# Microcontroller_and_Memory.net
KiCad netlist of a schematic drawn in Altium Designer
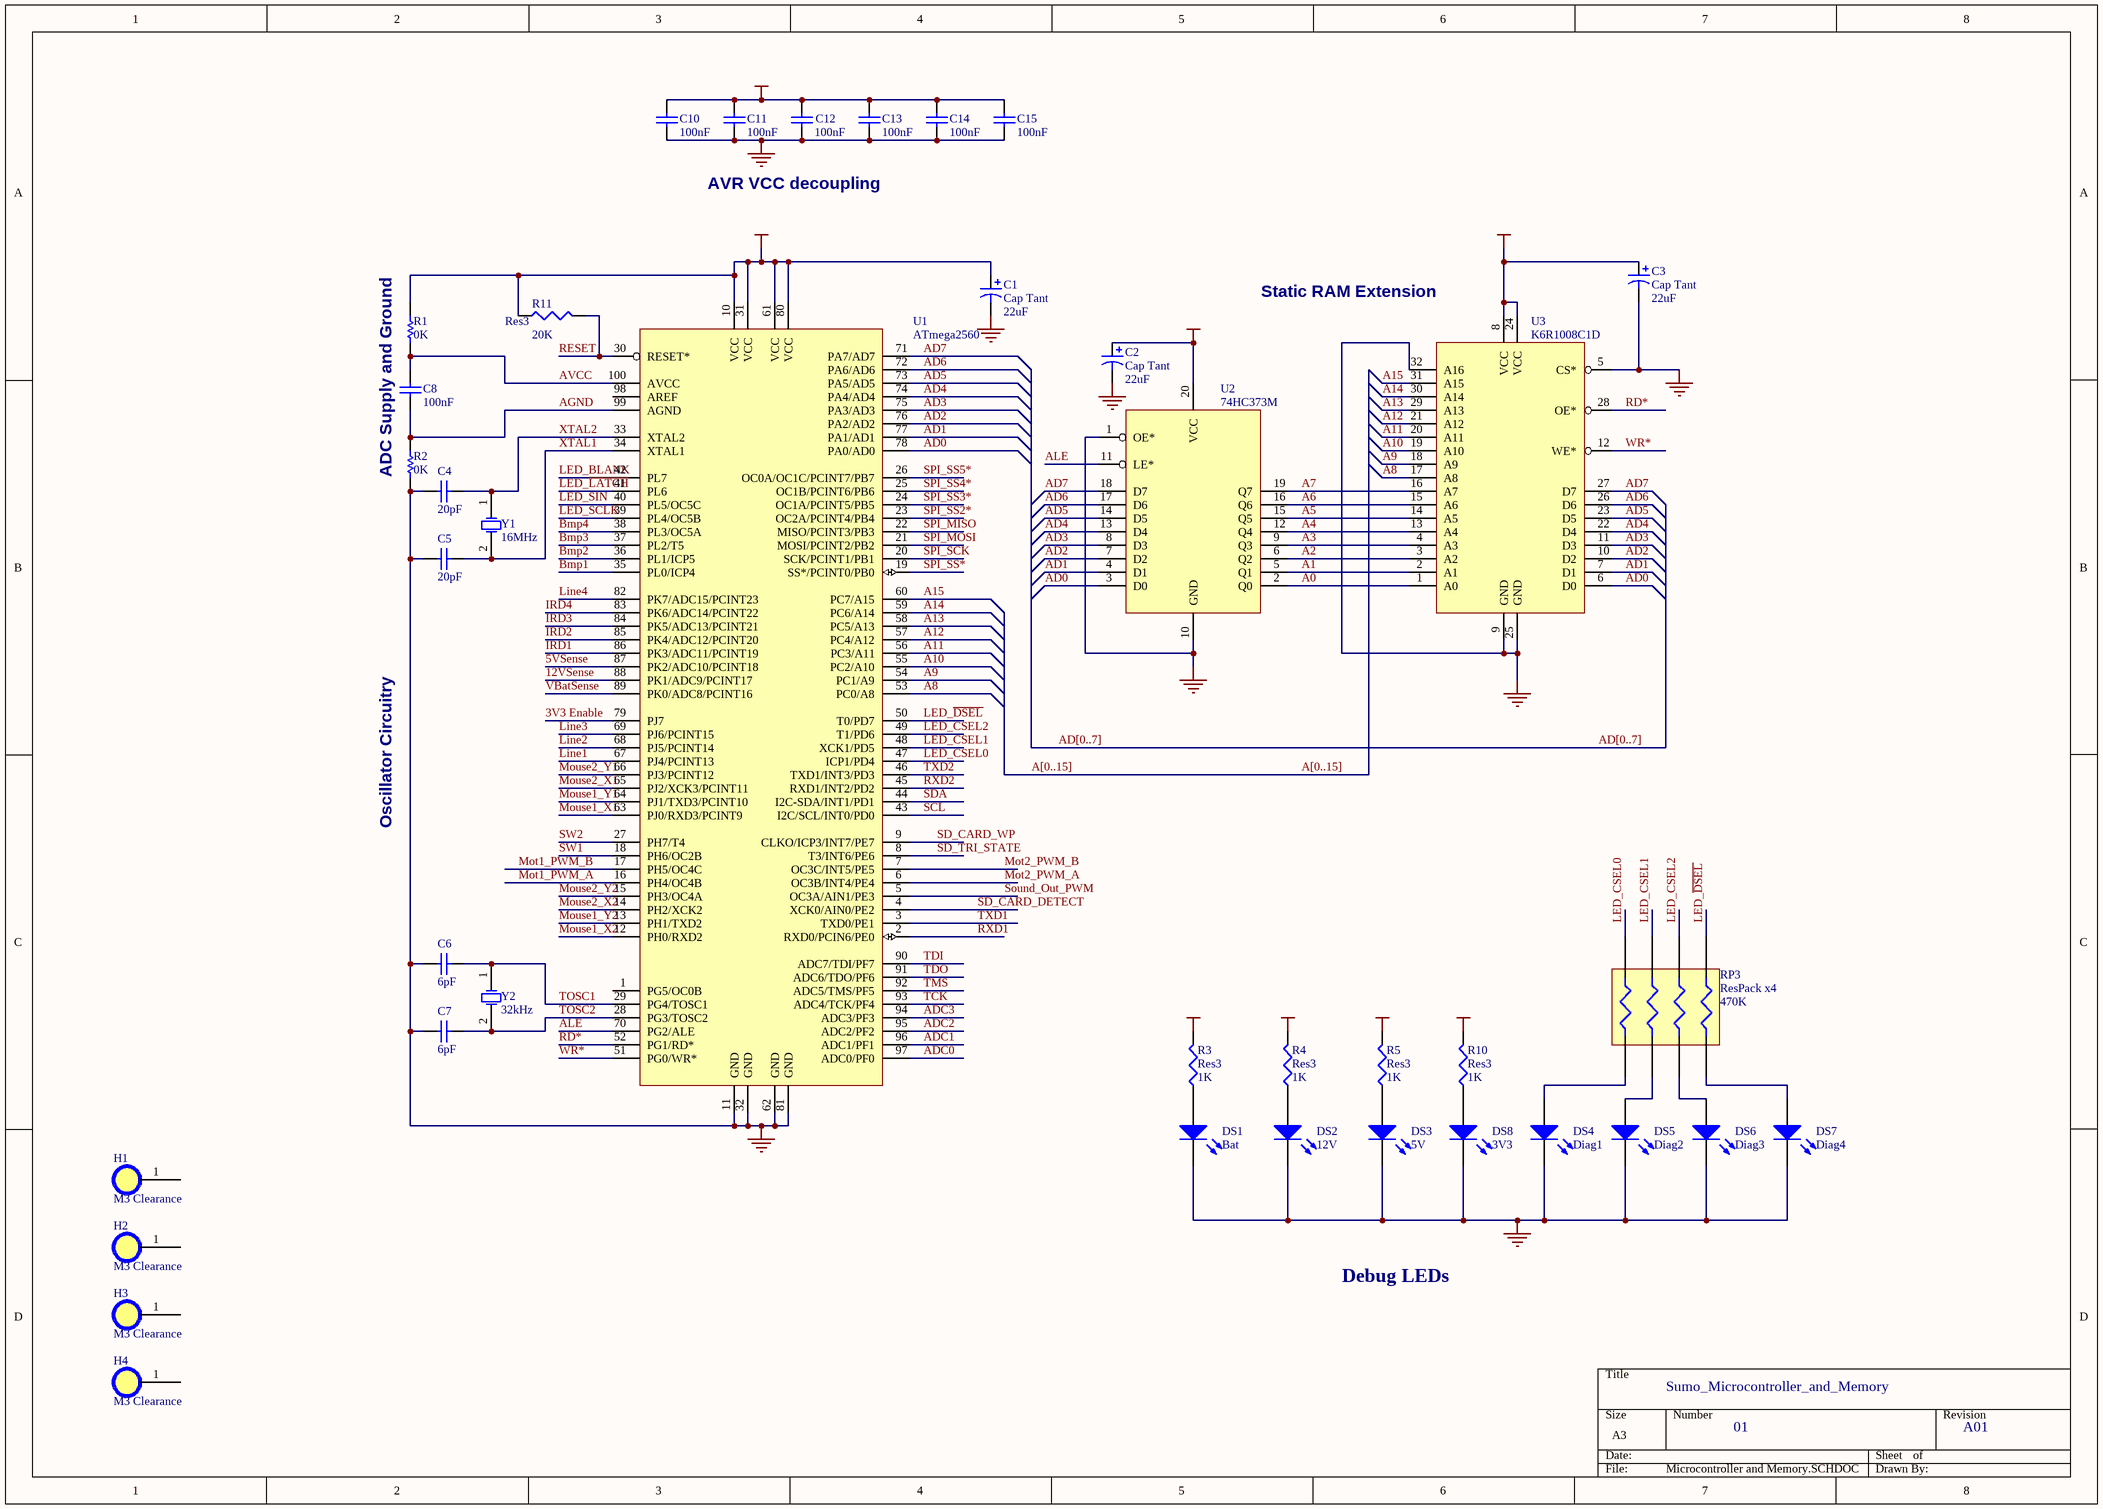
[diagram p0: Microcontroller and Memory.SCHDOC]

(export (version "E")
  (design (tool "Eeschema 10.0.6"))
  (components
    (comp (ref "C1")
      (value "Cap Tant")
      (footprint "CC4532-1812")
      (description "Polarized Capacitor (Axial)")
      (fields (field (name "ALTIUM_VALUE") "22uF") (field (name "PUBLISHER") "Altium Limited"))
      (libsource (lib "Miscellaneous Devices") (part "Cap Pol2"))
    )
    (comp (ref "C2")
      (value "Cap Tant")
      (footprint "CC4532-1812")
      (description "Polarized Capacitor (Axial)")
      (fields (field (name "ALTIUM_VALUE") "22uF") (field (name "PUBLISHER") "Altium Limited"))
      (libsource (lib "Miscellaneous Devices") (part "Cap Pol2"))
    )
    (comp (ref "C3")
      (value "Cap Tant")
      (footprint "CC4532-1812")
      (description "Polarized Capacitor (Axial)")
      (fields (field (name "ALTIUM_VALUE") "22uF") (field (name "PUBLISHER") "Altium Limited"))
      (libsource (lib "Miscellaneous Devices") (part "Cap Pol2"))
    )
    (comp (ref "C4")
      (value "20pF")
      (footprint "CC2012-0805")
      (description "Capacitor")
      (fields (field (name "PUBLISHER") "Altium Limited"))
      (libsource (lib "Miscellaneous Devices") (part "Cap"))
    )
    (comp (ref "C5")
      (value "20pF")
      (footprint "CC2012-0805")
      (description "Capacitor")
      (fields (field (name "PUBLISHER") "Altium Limited"))
      (libsource (lib "Miscellaneous Devices") (part "Cap"))
    )
    (comp (ref "C6")
      (value "6pF")
      (footprint "CC2012-0805")
      (description "Capacitor")
      (fields (field (name "PUBLISHER") "Altium Limited"))
      (libsource (lib "Miscellaneous Devices") (part "Cap"))
    )
    (comp (ref "C7")
      (value "6pF")
      (footprint "CC2012-0805")
      (description "Capacitor")
      (fields (field (name "PUBLISHER") "Altium Limited"))
      (libsource (lib "Miscellaneous Devices") (part "Cap"))
    )
    (comp (ref "C8")
      (value "100nF")
      (footprint "CC2012-0805")
      (description "Capacitor")
      (fields (field (name "PUBLISHER") "Altium Limited"))
      (libsource (lib "Miscellaneous Devices") (part "Cap"))
    )
    (comp (ref "C10")
      (value "100nF")
      (footprint "CC2012-0805")
      (description "Capacitor (Semiconductor SIM Model)")
      (fields (field (name "Comment") "Cap Semi") (field (name "PUBLISHER") "Altium Limited"))
      (libsource (lib "Miscellaneous Devices") (part "Cap Semi"))
    )
    (comp (ref "C11")
      (value "100nF")
      (footprint "CC2012-0805")
      (description "Capacitor (Semiconductor SIM Model)")
      (fields (field (name "Comment") "Cap Semi") (field (name "PUBLISHER") "Altium Limited"))
      (libsource (lib "Miscellaneous Devices") (part "Cap Semi"))
    )
    (comp (ref "C12")
      (value "100nF")
      (footprint "CC2012-0805")
      (description "Capacitor (Semiconductor SIM Model)")
      (fields (field (name "Comment") "Cap Semi") (field (name "PUBLISHER") "Altium Limited"))
      (libsource (lib "Miscellaneous Devices") (part "Cap Semi"))
    )
    (comp (ref "C13")
      (value "100nF")
      (footprint "CC2012-0805")
      (description "Capacitor (Semiconductor SIM Model)")
      (fields (field (name "Comment") "Cap Semi") (field (name "PUBLISHER") "Altium Limited"))
      (libsource (lib "Miscellaneous Devices") (part "Cap Semi"))
    )
    (comp (ref "C14")
      (value "100nF")
      (footprint "CC2012-0805")
      (description "Capacitor (Semiconductor SIM Model)")
      (fields (field (name "Comment") "Cap Semi") (field (name "PUBLISHER") "Altium Limited"))
      (libsource (lib "Miscellaneous Devices") (part "Cap Semi"))
    )
    (comp (ref "C15")
      (value "100nF")
      (footprint "CC2012-0805")
      (description "Capacitor (Semiconductor SIM Model)")
      (fields (field (name "Comment") "Cap Semi") (field (name "PUBLISHER") "Altium Limited"))
      (libsource (lib "Miscellaneous Devices") (part "Cap Semi"))
    )
    (comp (ref "DS1")
      (value "Bat")
      (footprint "SMD _LED")
      (description "Typical BLUE SiC LED")
      (fields (field (name "PUBLISHER") "Altium Limited"))
      (libsource (lib "Miscellaneous Devices") (part "LED3"))
    )
    (comp (ref "DS2")
      (value "12V")
      (footprint "SMD _LED")
      (description "Typical BLUE SiC LED")
      (fields (field (name "PUBLISHER") "Altium Limited"))
      (libsource (lib "Miscellaneous Devices") (part "LED3"))
    )
    (comp (ref "DS3")
      (value "5V")
      (footprint "SMD _LED")
      (description "Typical BLUE SiC LED")
      (fields (field (name "PUBLISHER") "Altium Limited"))
      (libsource (lib "Miscellaneous Devices") (part "LED3"))
    )
    (comp (ref "DS4")
      (value "Diag1")
      (footprint "SMD _LED")
      (description "Typical BLUE SiC LED")
      (fields (field (name "PUBLISHER") "Altium Limited"))
      (libsource (lib "Miscellaneous Devices") (part "LED3"))
    )
    (comp (ref "DS5")
      (value "Diag2")
      (footprint "SMD _LED")
      (description "Typical BLUE SiC LED")
      (fields (field (name "PUBLISHER") "Altium Limited"))
      (libsource (lib "Miscellaneous Devices") (part "LED3"))
    )
    (comp (ref "DS6")
      (value "Diag3")
      (footprint "SMD _LED")
      (description "Typical BLUE SiC LED")
      (fields (field (name "PUBLISHER") "Altium Limited"))
      (libsource (lib "Miscellaneous Devices") (part "LED3"))
    )
    (comp (ref "DS7")
      (value "Diag4")
      (footprint "SMD _LED")
      (description "Typical BLUE SiC LED")
      (fields (field (name "PUBLISHER") "Altium Limited"))
      (libsource (lib "Miscellaneous Devices") (part "LED3"))
    )
    (comp (ref "DS8")
      (value "3V3")
      (footprint "SMD _LED")
      (description "Typical BLUE SiC LED")
      (fields (field (name "PUBLISHER") "Altium Limited"))
      (libsource (lib "Miscellaneous Devices") (part "LED3"))
    )
    (comp (ref "H1")
      (value "M3 Clearance")
      (footprint "M3 Clearance")
      (description "3.2mm ID clearance hole for M3 screw")
      (libsource (lib "Sumo") (part "M3 Clearance hole"))
    )
    (comp (ref "H2")
      (value "M3 Clearance")
      (footprint "M3 Clearance")
      (description "3.2mm ID clearance hole for M3 screw")
      (libsource (lib "Sumo") (part "M3 Clearance hole"))
    )
    (comp (ref "H3")
      (value "M3 Clearance")
      (footprint "M3 Clearance")
      (description "3.2mm ID clearance hole for M3 screw")
      (libsource (lib "Sumo") (part "M3 Clearance hole"))
    )
    (comp (ref "H4")
      (value "M3 Clearance")
      (footprint "M3 Clearance")
      (description "3.2mm ID clearance hole for M3 screw")
      (libsource (lib "Sumo") (part "M3 Clearance hole"))
    )
    (comp (ref "R1")
      (value "0K")
      (footprint "R2012-0805")
      (description "Resistor")
      (fields (field (name "PUBLISHER") "Altium Limited"))
      (libsource (lib "Miscellaneous Devices") (part "Res1"))
    )
    (comp (ref "R2")
      (value "0K")
      (footprint "R2012-0805")
      (description "Resistor")
      (fields (field (name "PUBLISHER") "Altium Limited"))
      (libsource (lib "Miscellaneous Devices") (part "Res1"))
    )
    (comp (ref "R3")
      (value "Res3")
      (footprint "R2012-0805")
      (description "Resistor")
      (fields (field (name "ALTIUM_VALUE") "1K") (field (name "PUBLISHER") "Altium Limited"))
      (libsource (lib "Miscellaneous Devices") (part "Res3"))
    )
    (comp (ref "R4")
      (value "Res3")
      (footprint "R2012-0805")
      (description "Resistor")
      (fields (field (name "ALTIUM_VALUE") "1K") (field (name "PUBLISHER") "Altium Limited"))
      (libsource (lib "Miscellaneous Devices") (part "Res3"))
    )
    (comp (ref "R5")
      (value "Res3")
      (footprint "R2012-0805")
      (description "Resistor")
      (fields (field (name "ALTIUM_VALUE") "1K") (field (name "PUBLISHER") "Altium Limited"))
      (libsource (lib "Miscellaneous Devices") (part "Res3"))
    )
    (comp (ref "R10")
      (value "Res3")
      (footprint "R2012-0805")
      (description "Resistor")
      (fields (field (name "ALTIUM_VALUE") "1K") (field (name "PUBLISHER") "Altium Limited"))
      (libsource (lib "Miscellaneous Devices") (part "Res3"))
    )
    (comp (ref "R11")
      (value "Res3")
      (footprint "R2012-0805")
      (description "Resistor")
      (fields (field (name "ALTIUM_VALUE") "20K") (field (name "PUBLISHER") "Altium Limited"))
      (libsource (lib "Miscellaneous Devices") (part "Res3"))
    )
    (comp (ref "RP3")
      (value "ResPack x4")
      (footprint "4x0805 Resistor pack")
      (fields (field (name "ALTIUM_VALUE") "470K"))
      (libsource (lib "Sumo") (part "ResPack x4"))
    )
    (comp (ref "U1")
      (value "ATmega2560")
      (footprint "F-QFP14X14-G100/Z17N")
      (description "Atmel ATmega2560 MCU")
      (libsource (lib "Sumo") (part "ATmega2560"))
    )
    (comp (ref "U2")
      (value "74HC373M")
      (footprint "SO-G20/Y1.45")
      (description "Octal 8-bit D-type Latch")
      (libsource (lib "Schematic Library") (part "74373"))
    )
    (comp (ref "U3")
      (value "K6R1008C1D")
      (footprint "SO-G32/Y1.45")
      (description "Samsung 128Kx8 High-Speed Static RAM")
      (libsource (lib "Schematic Library") (part "K6R1008C1D"))
    )
    (comp (ref "Y1")
      (value "16MHz")
      (footprint "Crystal HC49SLF")
      (description "Crystal Oscillator")
      (fields (field (name "PUBLISHER") "Altium Limited"))
      (libsource (lib "Miscellaneous Devices") (part "XTAL"))
    )
    (comp (ref "Y2")
      (value "32kHz")
      (footprint "Crystal CFS206")
      (description "Crystal Oscillator")
      (fields (field (name "PUBLISHER") "Altium Limited"))
      (libsource (lib "Miscellaneous Devices") (part "XTAL"))
    )
  )
  (nets
    (net (code "1") (name "/3V3 Enable") (class "Default")
      (node (ref "U1") (pin "79") (pinfunction "PJ7_79") (pintype "passive"))
    )
    (net (code "2") (name "/5VSense") (class "Default")
      (node (ref "U1") (pin "87") (pinfunction "PK2/ADC10/PCINT18_87") (pintype "passive"))
    )
    (net (code "3") (name "/12VSense") (class "Default")
      (node (ref "U1") (pin "88") (pinfunction "PK1/ADC9/PCINT17_88") (pintype "passive"))
    )
    (net (code "4") (name "/A0") (class "Default")
      (node (ref "U2") (pin "2") (pinfunction "Q0_2") (pintype "passive"))
      (node (ref "U3") (pin "1") (pinfunction "A0_1") (pintype "passive"))
    )
    (net (code "5") (name "/A1") (class "Default")
      (node (ref "U2") (pin "5") (pinfunction "Q1_5") (pintype "passive"))
      (node (ref "U3") (pin "2") (pinfunction "A1_2") (pintype "passive"))
    )
    (net (code "6") (name "/A2") (class "Default")
      (node (ref "U2") (pin "6") (pinfunction "Q2_6") (pintype "passive"))
      (node (ref "U3") (pin "3") (pinfunction "A2_3") (pintype "passive"))
    )
    (net (code "7") (name "/A3") (class "Default")
      (node (ref "U2") (pin "9") (pinfunction "Q3_9") (pintype "passive"))
      (node (ref "U3") (pin "4") (pinfunction "A3_4") (pintype "passive"))
    )
    (net (code "8") (name "/A4") (class "Default")
      (node (ref "U2") (pin "12") (pinfunction "Q4_12") (pintype "passive"))
      (node (ref "U3") (pin "13") (pinfunction "A4_13") (pintype "passive"))
    )
    (net (code "9") (name "/A5") (class "Default")
      (node (ref "U2") (pin "15") (pinfunction "Q5_15") (pintype "passive"))
      (node (ref "U3") (pin "14") (pinfunction "A5_14") (pintype "passive"))
    )
    (net (code "10") (name "/A6") (class "Default")
      (node (ref "U2") (pin "16") (pinfunction "Q6_16") (pintype "passive"))
      (node (ref "U3") (pin "15") (pinfunction "A6_15") (pintype "passive"))
    )
    (net (code "11") (name "/A7") (class "Default")
      (node (ref "U2") (pin "19") (pinfunction "Q7_19") (pintype "passive"))
      (node (ref "U3") (pin "16") (pinfunction "A7_16") (pintype "passive"))
    )
    (net (code "12") (name "/A8") (class "Default")
      (node (ref "U1") (pin "53") (pinfunction "PC0/A8_53") (pintype "passive"))
      (node (ref "U3") (pin "17") (pinfunction "A8_17") (pintype "passive"))
    )
    (net (code "13") (name "/A9") (class "Default")
      (node (ref "U1") (pin "54") (pinfunction "PC1/A9_54") (pintype "passive"))
      (node (ref "U3") (pin "18") (pinfunction "A9_18") (pintype "passive"))
    )
    (net (code "14") (name "/A10") (class "Default")
      (node (ref "U1") (pin "55") (pinfunction "PC2/A10_55") (pintype "passive"))
      (node (ref "U3") (pin "19") (pinfunction "A10_19") (pintype "passive"))
    )
    (net (code "15") (name "/A11") (class "Default")
      (node (ref "U1") (pin "56") (pinfunction "PC3/A11_56") (pintype "passive"))
      (node (ref "U3") (pin "20") (pinfunction "A11_20") (pintype "passive"))
    )
    (net (code "16") (name "/A12") (class "Default")
      (node (ref "U1") (pin "57") (pinfunction "PC4/A12_57") (pintype "passive"))
      (node (ref "U3") (pin "21") (pinfunction "A12_21") (pintype "passive"))
    )
    (net (code "17") (name "/A13") (class "Default")
      (node (ref "U1") (pin "58") (pinfunction "PC5/A13_58") (pintype "passive"))
      (node (ref "U3") (pin "29") (pinfunction "A13_29") (pintype "passive"))
    )
    (net (code "18") (name "/A14") (class "Default")
      (node (ref "U1") (pin "59") (pinfunction "PC6/A14_59") (pintype "passive"))
      (node (ref "U3") (pin "30") (pinfunction "A14_30") (pintype "passive"))
    )
    (net (code "19") (name "/A15") (class "Default")
      (node (ref "U1") (pin "60") (pinfunction "PC7/A15_60") (pintype "passive"))
      (node (ref "U3") (pin "31") (pinfunction "A15_31") (pintype "passive"))
    )
    (net (code "20") (name "/AD0") (class "Default")
      (node (ref "U1") (pin "78") (pinfunction "PA0/AD0_78") (pintype "passive"))
      (node (ref "U2") (pin "3") (pinfunction "D0_3") (pintype "passive"))
      (node (ref "U3") (pin "6") (pinfunction "D0_6") (pintype "passive"))
    )
    (net (code "21") (name "/AD1") (class "Default")
      (node (ref "U1") (pin "77") (pinfunction "PA1/AD1_77") (pintype "passive"))
      (node (ref "U2") (pin "4") (pinfunction "D1_4") (pintype "passive"))
      (node (ref "U3") (pin "7") (pinfunction "D1_7") (pintype "passive"))
    )
    (net (code "22") (name "/AD2") (class "Default")
      (node (ref "U1") (pin "76") (pinfunction "PA2/AD2_76") (pintype "passive"))
      (node (ref "U2") (pin "7") (pinfunction "D2_7") (pintype "passive"))
      (node (ref "U3") (pin "10") (pinfunction "D2_10") (pintype "passive"))
    )
    (net (code "23") (name "/AD3") (class "Default")
      (node (ref "U1") (pin "75") (pinfunction "PA3/AD3_75") (pintype "passive"))
      (node (ref "U2") (pin "8") (pinfunction "D3_8") (pintype "passive"))
      (node (ref "U3") (pin "11") (pinfunction "D3_11") (pintype "passive"))
    )
    (net (code "24") (name "/AD4") (class "Default")
      (node (ref "U1") (pin "74") (pinfunction "PA4/AD4_74") (pintype "passive"))
      (node (ref "U2") (pin "13") (pinfunction "D4_13") (pintype "passive"))
      (node (ref "U3") (pin "22") (pinfunction "D4_22") (pintype "passive"))
    )
    (net (code "25") (name "/AD5") (class "Default")
      (node (ref "U1") (pin "73") (pinfunction "PA5/AD5_73") (pintype "passive"))
      (node (ref "U2") (pin "14") (pinfunction "D5_14") (pintype "passive"))
      (node (ref "U3") (pin "23") (pinfunction "D5_23") (pintype "passive"))
    )
    (net (code "26") (name "/AD6") (class "Default")
      (node (ref "U1") (pin "72") (pinfunction "PA6/AD6_72") (pintype "passive"))
      (node (ref "U2") (pin "17") (pinfunction "D6_17") (pintype "passive"))
      (node (ref "U3") (pin "26") (pinfunction "D6_26") (pintype "passive"))
    )
    (net (code "27") (name "/AD7") (class "Default")
      (node (ref "U1") (pin "71") (pinfunction "PA7/AD7_71") (pintype "passive"))
      (node (ref "U2") (pin "18") (pinfunction "D7_18") (pintype "passive"))
      (node (ref "U3") (pin "27") (pinfunction "D7_27") (pintype "passive"))
    )
    (net (code "28") (name "/ADC0") (class "Default")
      (node (ref "U1") (pin "97") (pinfunction "ADC0/PF0_97") (pintype "passive"))
    )
    (net (code "29") (name "/ADC1") (class "Default")
      (node (ref "U1") (pin "96") (pinfunction "ADC1/PF1_96") (pintype "passive"))
    )
    (net (code "30") (name "/ADC2") (class "Default")
      (node (ref "U1") (pin "95") (pinfunction "ADC2/PF2_95") (pintype "passive"))
    )
    (net (code "31") (name "/ADC3") (class "Default")
      (node (ref "U1") (pin "94") (pinfunction "ADC3/PF3_94") (pintype "passive"))
    )
    (net (code "33") (name "/AGND") (class "Default")
      (node (ref "C8") (pin "2") (pinfunction "2_2") (pintype "passive"))
      (node (ref "R2") (pin "2") (pinfunction "2_2") (pintype "passive"))
      (node (ref "U1") (pin "99") (pinfunction "AGND_99") (pintype "passive"))
    )
    (net (code "34") (name "/ALE") (class "Default")
      (node (ref "U1") (pin "70") (pinfunction "PG2/ALE_70") (pintype "passive"))
      (node (ref "U2") (pin "11") (pinfunction "LE*_11") (pintype "passive"))
    )
    (net (code "35") (name "/AVCC") (class "Default")
      (node (ref "C8") (pin "1") (pinfunction "1_1") (pintype "passive"))
      (node (ref "R1") (pin "1") (pinfunction "1_1") (pintype "passive"))
      (node (ref "U1") (pin "100") (pinfunction "AVCC_100") (pintype "passive"))
    )
    (net (code "37") (name "/Bmp1") (class "Default")
      (node (ref "U1") (pin "35") (pinfunction "PL0/ICP4_35") (pintype "passive"))
    )
    (net (code "38") (name "/Bmp2") (class "Default")
      (node (ref "U1") (pin "36") (pinfunction "PL1/ICP5_36") (pintype "passive"))
    )
    (net (code "39") (name "/Bmp3") (class "Default")
      (node (ref "U1") (pin "37") (pinfunction "PL2/T5_37") (pintype "passive"))
    )
    (net (code "40") (name "/Bmp4") (class "Default")
      (node (ref "U1") (pin "38") (pinfunction "PL3/OC5A_38") (pintype "passive"))
    )
    (net (code "41") (name "/IRD1") (class "Default")
      (node (ref "U1") (pin "86") (pinfunction "PK3/ADC11/PCINT19_86") (pintype "passive"))
    )
    (net (code "42") (name "/IRD2") (class "Default")
      (node (ref "U1") (pin "85") (pinfunction "PK4/ADC12/PCINT20_85") (pintype "passive"))
    )
    (net (code "43") (name "/IRD3") (class "Default")
      (node (ref "U1") (pin "84") (pinfunction "PK5/ADC13/PCINT21_84") (pintype "passive"))
    )
    (net (code "44") (name "/IRD4") (class "Default")
      (node (ref "U1") (pin "83") (pinfunction "PK6/ADC14/PCINT22_83") (pintype "passive"))
    )
    (net (code "45") (name "/LED_BLANK") (class "Default")
      (node (ref "U1") (pin "42") (pinfunction "PL7_42") (pintype "passive"))
    )
    (net (code "46") (name "/LED_CSEL0") (class "Default")
      (node (ref "RP3") (pin "8") (pintype "passive"))
      (node (ref "U1") (pin "47") (pinfunction "ICP1/PD4_47") (pintype "passive"))
    )
    (net (code "47") (name "/LED_CSEL1") (class "Default")
      (node (ref "RP3") (pin "7") (pintype "passive"))
      (node (ref "U1") (pin "48") (pinfunction "XCK1/PD5_48") (pintype "passive"))
    )
    (net (code "48") (name "/LED_CSEL2") (class "Default")
      (node (ref "RP3") (pin "6") (pintype "passive"))
      (node (ref "U1") (pin "49") (pinfunction "T1/PD6_49") (pintype "passive"))
    )
    (net (code "49") (name "/LED_SCLK") (class "Default")
      (node (ref "U1") (pin "39") (pinfunction "PL4/OC5B_39") (pintype "passive"))
    )
    (net (code "50") (name "/LED_SIN") (class "Default")
      (node (ref "U1") (pin "40") (pinfunction "PL5/OC5C_40") (pintype "passive"))
    )
    (net (code "51") (name "/LED_~{DSEL}") (class "Default")
      (node (ref "RP3") (pin "5") (pintype "passive"))
      (node (ref "U1") (pin "50") (pinfunction "T0/PD7_50") (pintype "passive"))
    )
    (net (code "52") (name "/LED_~{LATCH}") (class "Default")
      (node (ref "U1") (pin "41") (pinfunction "PL6_41") (pintype "passive"))
    )
    (net (code "53") (name "/Line1") (class "Default")
      (node (ref "U1") (pin "67") (pinfunction "PJ4/PCINT13_67") (pintype "passive"))
    )
    (net (code "54") (name "/Line2") (class "Default")
      (node (ref "U1") (pin "68") (pinfunction "PJ5/PCINT14_68") (pintype "passive"))
    )
    (net (code "55") (name "/Line3") (class "Default")
      (node (ref "U1") (pin "69") (pinfunction "PJ6/PCINT15_69") (pintype "passive"))
    )
    (net (code "56") (name "/Line4") (class "Default")
      (node (ref "U1") (pin "82") (pinfunction "PK7/ADC15/PCINT23_82") (pintype "passive"))
    )
    (net (code "57") (name "/Mot1_PWM_A") (class "Default")
      (node (ref "U1") (pin "16") (pinfunction "PH4/OC4B_16") (pintype "passive"))
    )
    (net (code "58") (name "/Mot1_PWM_B") (class "Default")
      (node (ref "U1") (pin "17") (pinfunction "PH5/OC4C_17") (pintype "passive"))
    )
    (net (code "59") (name "/Mot2_PWM_A") (class "Default")
      (node (ref "U1") (pin "6") (pinfunction "OC3B/INT4/PE4_6") (pintype "passive"))
    )
    (net (code "60") (name "/Mot2_PWM_B") (class "Default")
      (node (ref "U1") (pin "7") (pinfunction "OC3C/INT5/PE5_7") (pintype "passive"))
    )
    (net (code "61") (name "/Mouse1_X1") (class "Default")
      (node (ref "U1") (pin "63") (pinfunction "PJ0/RXD3/PCINT9_63") (pintype "passive"))
    )
    (net (code "62") (name "/Mouse1_X2") (class "Default")
      (node (ref "U1") (pin "12") (pinfunction "PH0/RXD2_12") (pintype "passive"))
    )
    (net (code "63") (name "/Mouse1_Y1") (class "Default")
      (node (ref "U1") (pin "64") (pinfunction "PJ1/TXD3/PCINT10_64") (pintype "passive"))
    )
    (net (code "64") (name "/Mouse1_Y2") (class "Default")
      (node (ref "U1") (pin "13") (pinfunction "PH1/TXD2_13") (pintype "passive"))
    )
    (net (code "65") (name "/Mouse2_X1") (class "Default")
      (node (ref "U1") (pin "65") (pinfunction "PJ2/XCK3/PCINT11_65") (pintype "passive"))
    )
    (net (code "66") (name "/Mouse2_X2") (class "Default")
      (node (ref "U1") (pin "14") (pinfunction "PH2/XCK2_14") (pintype "passive"))
    )
    (net (code "67") (name "/Mouse2_Y1") (class "Default")
      (node (ref "U1") (pin "66") (pinfunction "PJ3/PCINT12_66") (pintype "passive"))
    )
    (net (code "68") (name "/Mouse2_Y2") (class "Default")
      (node (ref "U1") (pin "15") (pinfunction "PH3/OC4A_15") (pintype "passive"))
    )
    (net (code "69") (name "/RD*") (class "Default")
      (node (ref "U1") (pin "52") (pinfunction "PG1/RD*_52") (pintype "passive"))
      (node (ref "U3") (pin "28") (pinfunction "OE*_28") (pintype "passive"))
    )
    (net (code "70") (name "/RESET") (class "Default")
      (node (ref "R11") (pin "2") (pinfunction "2_2") (pintype "passive"))
      (node (ref "U1") (pin "30") (pinfunction "RESET*_30") (pintype "passive"))
    )
    (net (code "71") (name "/RXD1") (class "Default")
      (node (ref "U1") (pin "2") (pinfunction "RXD0/PCIN6/PE0_2") (pintype "bidirectional"))
    )
    (net (code "72") (name "/RXD2") (class "Default")
      (node (ref "U1") (pin "45") (pinfunction "RXD1/INT2/PD2_45") (pintype "passive"))
    )
    (net (code "73") (name "/SCL") (class "Default")
      (node (ref "U1") (pin "43") (pinfunction "I2C/SCL/INT0/PD0_43") (pintype "passive"))
    )
    (net (code "74") (name "/SDA") (class "Default")
      (node (ref "U1") (pin "44") (pinfunction "I2C-SDA/INT1/PD1_44") (pintype "passive"))
    )
    (net (code "75") (name "/SD_CARD_DETECT") (class "Default")
      (node (ref "U1") (pin "4") (pinfunction "XCK0/AIN0/PE2_4") (pintype "passive"))
    )
    (net (code "76") (name "/SD_CARD_WP") (class "Default")
      (node (ref "U1") (pin "9") (pinfunction "CLKO/ICP3/INT7/PE7_9") (pintype "passive"))
    )
    (net (code "77") (name "/SD_TRI_STATE") (class "Default")
      (node (ref "U1") (pin "8") (pinfunction "T3/INT6/PE6_8") (pintype "passive"))
    )
    (net (code "78") (name "/SPI_MISO") (class "Default")
      (node (ref "U1") (pin "22") (pinfunction "MISO/PCINT3/PB3_22") (pintype "passive"))
    )
    (net (code "79") (name "/SPI_MOSI") (class "Default")
      (node (ref "U1") (pin "21") (pinfunction "MOSI/PCINT2/PB2_21") (pintype "passive"))
    )
    (net (code "80") (name "/SPI_SCK") (class "Default")
      (node (ref "U1") (pin "20") (pinfunction "SCK/PCINT1/PB1_20") (pintype "passive"))
    )
    (net (code "81") (name "/SPI_SS*") (class "Default")
      (node (ref "U1") (pin "19") (pinfunction "SS*/PCINT0/PB0_19") (pintype "bidirectional"))
    )
    (net (code "82") (name "/SPI_SS2*") (class "Default")
      (node (ref "U1") (pin "23") (pinfunction "OC2A/PCINT4/PB4_23") (pintype "passive"))
    )
    (net (code "83") (name "/SPI_SS3*") (class "Default")
      (node (ref "U1") (pin "24") (pinfunction "OC1A/PCINT5/PB5_24") (pintype "passive"))
    )
    (net (code "84") (name "/SPI_SS4*") (class "Default")
      (node (ref "U1") (pin "25") (pinfunction "OC1B/PCINT6/PB6_25") (pintype "passive"))
    )
    (net (code "85") (name "/SPI_SS5*") (class "Default")
      (node (ref "U1") (pin "26") (pinfunction "OC0A/OC1C/PCINT7/PB7_26") (pintype "passive"))
    )
    (net (code "86") (name "/SW1") (class "Default")
      (node (ref "U1") (pin "18") (pinfunction "PH6/OC2B_18") (pintype "passive"))
    )
    (net (code "87") (name "/SW2") (class "Default")
      (node (ref "U1") (pin "27") (pinfunction "PH7/T4_27") (pintype "passive"))
    )
    (net (code "88") (name "/Sound_Out_PWM") (class "Default")
      (node (ref "U1") (pin "5") (pinfunction "OC3A/AIN1/PE3_5") (pintype "passive"))
    )
    (net (code "89") (name "/TCK") (class "Default")
      (node (ref "U1") (pin "93") (pinfunction "ADC4/TCK/PF4_93") (pintype "passive"))
    )
    (net (code "90") (name "/TDI") (class "Default")
      (node (ref "U1") (pin "90") (pinfunction "ADC7/TDI/PF7_90") (pintype "passive"))
    )
    (net (code "91") (name "/TDO") (class "Default")
      (node (ref "U1") (pin "91") (pinfunction "ADC6/TDO/PF6_91") (pintype "passive"))
    )
    (net (code "92") (name "/TMS") (class "Default")
      (node (ref "U1") (pin "92") (pinfunction "ADC5/TMS/PF5_92") (pintype "passive"))
    )
    (net (code "93") (name "/TOSC1") (class "Default")
      (node (ref "C6") (pin "2") (pinfunction "2_2") (pintype "passive"))
      (node (ref "U1") (pin "29") (pinfunction "PG4/TOSC1_29") (pintype "passive"))
      (node (ref "Y2") (pin "1") (pinfunction "OSC1_1") (pintype "passive"))
    )
    (net (code "94") (name "/TOSC2") (class "Default")
      (node (ref "C7") (pin "2") (pinfunction "2_2") (pintype "passive"))
      (node (ref "U1") (pin "28") (pinfunction "PG3/TOSC2_28") (pintype "passive"))
      (node (ref "Y2") (pin "2") (pinfunction "OSC2_2") (pintype "passive"))
    )
    (net (code "95") (name "/TXD1") (class "Default")
      (node (ref "U1") (pin "3") (pinfunction "TXD0/PE1_3") (pintype "passive"))
    )
    (net (code "96") (name "/TXD2") (class "Default")
      (node (ref "U1") (pin "46") (pinfunction "TXD1/INT3/PD3_46") (pintype "passive"))
    )
    (net (code "97") (name "/VBatSense") (class "Default")
      (node (ref "U1") (pin "89") (pinfunction "PK0/ADC8/PCINT16_89") (pintype "passive"))
    )
    (net (code "98") (name "/WR*") (class "Default")
      (node (ref "U1") (pin "51") (pinfunction "PG0/WR*_51") (pintype "passive"))
      (node (ref "U3") (pin "12") (pinfunction "WE*_12") (pintype "passive"))
    )
    (net (code "99") (name "/XTAL1") (class "Default")
      (node (ref "C5") (pin "2") (pinfunction "2_2") (pintype "passive"))
      (node (ref "U1") (pin "34") (pinfunction "XTAL1_34") (pintype "passive"))
      (node (ref "Y1") (pin "2") (pinfunction "OSC2_2") (pintype "passive"))
    )
    (net (code "100") (name "/XTAL2") (class "Default")
      (node (ref "C4") (pin "2") (pinfunction "2_2") (pintype "passive"))
      (node (ref "U1") (pin "33") (pinfunction "XTAL2_33") (pintype "passive"))
      (node (ref "Y1") (pin "1") (pinfunction "OSC1_1") (pintype "passive"))
    )
    (net (code "101") (name "3V3") (class "Default")
      (node (ref "R10") (pin "2") (pinfunction "2_2") (pintype "passive"))
    )
    (net (code "102") (name "5V") (class "Default")
      (node (ref "C1") (pin "1") (pinfunction "1_1") (pintype "passive"))
      (node (ref "C10") (pin "2") (pinfunction "2_2") (pintype "passive"))
      (node (ref "C11") (pin "2") (pinfunction "2_2") (pintype "passive"))
      (node (ref "C12") (pin "2") (pinfunction "2_2") (pintype "passive"))
      (node (ref "C13") (pin "2") (pinfunction "2_2") (pintype "passive"))
      (node (ref "C14") (pin "2") (pinfunction "2_2") (pintype "passive"))
      (node (ref "C15") (pin "2") (pinfunction "2_2") (pintype "passive"))
      (node (ref "C2") (pin "1") (pinfunction "1_1") (pintype "passive"))
      (node (ref "C3") (pin "1") (pinfunction "1_1") (pintype "passive"))
      (node (ref "R1") (pin "2") (pinfunction "2_2") (pintype "passive"))
      (node (ref "R11") (pin "1") (pinfunction "1_1") (pintype "passive"))
      (node (ref "R5") (pin "2") (pinfunction "2_2") (pintype "passive"))
      (node (ref "U1") (pin "10") (pinfunction "VCC_10") (pintype "passive"))
      (node (ref "U1") (pin "31") (pinfunction "VCC_31") (pintype "passive"))
      (node (ref "U1") (pin "61") (pinfunction "VCC_61") (pintype "passive"))
      (node (ref "U1") (pin "80") (pinfunction "VCC_80") (pintype "passive"))
      (node (ref "U2") (pin "20") (pinfunction "VCC_20") (pintype "passive"))
      (node (ref "U3") (pin "24") (pinfunction "VCC_24") (pintype "passive"))
      (node (ref "U3") (pin "8") (pinfunction "VCC_8") (pintype "passive"))
    )
    (net (code "103") (name "12V") (class "Default")
      (node (ref "R4") (pin "2") (pinfunction "2_2") (pintype "passive"))
    )
    (net (code "104") (name "GND") (class "Default")
      (node (ref "C1") (pin "2") (pinfunction "2_2") (pintype "passive"))
      (node (ref "C10") (pin "1") (pinfunction "1_1") (pintype "passive"))
      (node (ref "C11") (pin "1") (pinfunction "1_1") (pintype "passive"))
      (node (ref "C12") (pin "1") (pinfunction "1_1") (pintype "passive"))
      (node (ref "C13") (pin "1") (pinfunction "1_1") (pintype "passive"))
      (node (ref "C14") (pin "1") (pinfunction "1_1") (pintype "passive"))
      (node (ref "C15") (pin "1") (pinfunction "1_1") (pintype "passive"))
      (node (ref "C2") (pin "2") (pinfunction "2_2") (pintype "passive"))
      (node (ref "C3") (pin "2") (pinfunction "2_2") (pintype "passive"))
      (node (ref "C4") (pin "1") (pinfunction "1_1") (pintype "passive"))
      (node (ref "C5") (pin "1") (pinfunction "1_1") (pintype "passive"))
      (node (ref "C6") (pin "1") (pinfunction "1_1") (pintype "passive"))
      (node (ref "C7") (pin "1") (pinfunction "1_1") (pintype "passive"))
      (node (ref "DS1") (pin "2") (pinfunction "K_2") (pintype "passive"))
      (node (ref "DS2") (pin "2") (pinfunction "K_2") (pintype "passive"))
      (node (ref "DS3") (pin "2") (pinfunction "K_2") (pintype "passive"))
      (node (ref "DS4") (pin "2") (pinfunction "K_2") (pintype "passive"))
      (node (ref "DS5") (pin "2") (pinfunction "K_2") (pintype "passive"))
      (node (ref "DS6") (pin "2") (pinfunction "K_2") (pintype "passive"))
      (node (ref "DS7") (pin "2") (pinfunction "K_2") (pintype "passive"))
      (node (ref "DS8") (pin "2") (pinfunction "K_2") (pintype "passive"))
      (node (ref "R2") (pin "1") (pinfunction "1_1") (pintype "passive"))
      (node (ref "U1") (pin "11") (pinfunction "GND_11") (pintype "passive"))
      (node (ref "U1") (pin "32") (pinfunction "GND_32") (pintype "passive"))
      (node (ref "U1") (pin "62") (pinfunction "GND_62") (pintype "passive"))
      (node (ref "U1") (pin "81") (pinfunction "GND_81") (pintype "passive"))
      (node (ref "U2") (pin "1") (pinfunction "OE*_1") (pintype "passive"))
      (node (ref "U2") (pin "10") (pinfunction "GND_10") (pintype "passive"))
      (node (ref "U3") (pin "25") (pinfunction "GND_25") (pintype "passive"))
      (node (ref "U3") (pin "32") (pinfunction "A16_32") (pintype "passive"))
      (node (ref "U3") (pin "5") (pinfunction "CS*_5") (pintype "passive"))
      (node (ref "U3") (pin "9") (pinfunction "GND_9") (pintype "passive"))
    )
    (net (code "105") (name "Net-(DS1-A)") (class "Default")
      (node (ref "DS1") (pin "1") (pinfunction "A_1") (pintype "passive"))
      (node (ref "R3") (pin "1") (pinfunction "1_1") (pintype "passive"))
    )
    (net (code "106") (name "Net-(DS2-A)") (class "Default")
      (node (ref "DS2") (pin "1") (pinfunction "A_1") (pintype "passive"))
      (node (ref "R4") (pin "1") (pinfunction "1_1") (pintype "passive"))
    )
    (net (code "107") (name "Net-(DS3-A)") (class "Default")
      (node (ref "DS3") (pin "1") (pinfunction "A_1") (pintype "passive"))
      (node (ref "R5") (pin "1") (pinfunction "1_1") (pintype "passive"))
    )
    (net (code "108") (name "Net-(DS4-A)") (class "Default")
      (node (ref "DS4") (pin "1") (pinfunction "A_1") (pintype "passive"))
      (node (ref "RP3") (pin "1") (pintype "passive"))
    )
    (net (code "109") (name "Net-(DS5-A)") (class "Default")
      (node (ref "DS5") (pin "1") (pinfunction "A_1") (pintype "passive"))
      (node (ref "RP3") (pin "2") (pintype "passive"))
    )
    (net (code "110") (name "Net-(DS6-A)") (class "Default")
      (node (ref "DS6") (pin "1") (pinfunction "A_1") (pintype "passive"))
      (node (ref "RP3") (pin "3") (pintype "passive"))
    )
    (net (code "111") (name "Net-(DS7-A)") (class "Default")
      (node (ref "DS7") (pin "1") (pinfunction "A_1") (pintype "passive"))
      (node (ref "RP3") (pin "4") (pintype "passive"))
    )
    (net (code "112") (name "Net-(DS8-A)") (class "Default")
      (node (ref "DS8") (pin "1") (pinfunction "A_1") (pintype "passive"))
      (node (ref "R10") (pin "1") (pinfunction "1_1") (pintype "passive"))
    )
    (net (code "113") (name "VBat") (class "Default")
      (node (ref "R3") (pin "2") (pinfunction "2_2") (pintype "passive"))
    )
    (net (code "114") (name "unconnected-(H1-Pad1)") (class "Default")
      (node (ref "H1") (pin "1") (pintype "passive"))
    )
    (net (code "115") (name "unconnected-(H2-Pad1)") (class "Default")
      (node (ref "H2") (pin "1") (pintype "passive"))
    )
    (net (code "116") (name "unconnected-(H3-Pad1)") (class "Default")
      (node (ref "H3") (pin "1") (pintype "passive"))
    )
    (net (code "117") (name "unconnected-(H4-Pad1)") (class "Default")
      (node (ref "H4") (pin "1") (pintype "passive"))
    )
    (net (code "118") (name "unconnected-(U1-AREF-Pad98)") (class "Default")
      (node (ref "U1") (pin "98") (pinfunction "AREF_98") (pintype "passive"))
    )
    (net (code "119") (name "unconnected-(U1-PG5{slash}OC0B-Pad1)") (class "Default")
      (node (ref "U1") (pin "1") (pinfunction "PG5/OC0B_1") (pintype "passive"))
    )
  )
)
